# Sheet1.net
KiCad netlist of a schematic drawn in Altium Designer
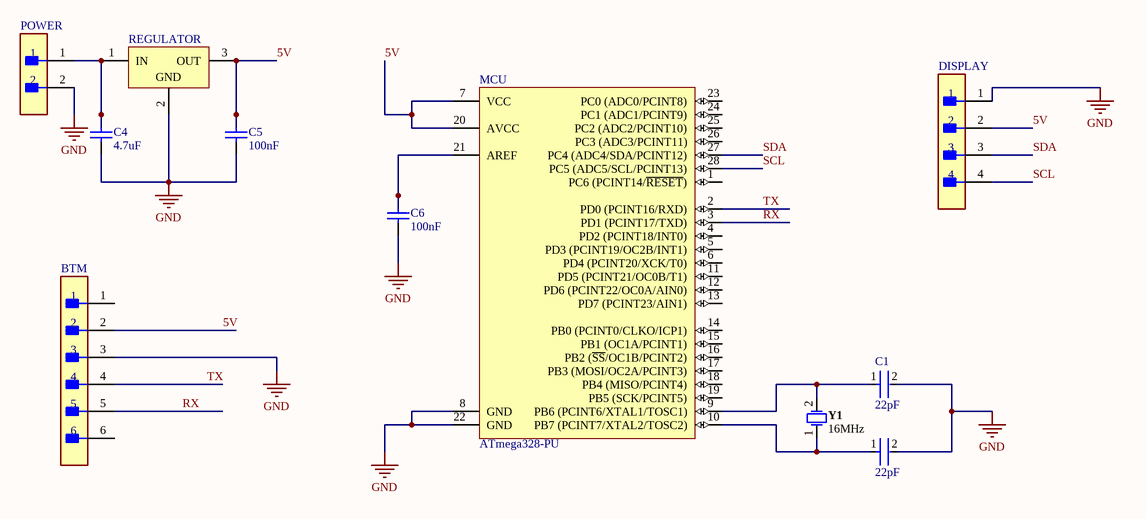
[diagram p0: Sheet1.SchDoc]

(export (version "E")
  (design (tool "Eeschema 10.0.6"))
  (components
    (comp (ref "BTM")
      (value "22-27-2061")
      (footprint "FP-22-27-2061-MFG")
      (description "CONN HEADER VERT 6POS 2.54MM")
      (libsource (lib "Altium Content Vault") (part "f2cb566baf1c37ab5a3b8e90bbeafd6"))
    )
    (comp (ref "C1")
      (value "22pF")
      (footprint "FP-RCE0K1-MFG")
      (description "Cap Ceramic 22pF 50V C0G ±5% Radial 5mm +125°C Automotive Bulk")
      (fields (field (name "TOLERANCE") "5%"))
      (libsource (lib "Altium Content Vault") (part "b4654b650e69147ec39a6b967a45e02"))
    )
    (comp (ref "C2")
      (value "22pF")
      (footprint "FP-RCE0K1-MFG")
      (description "Cap Ceramic 22pF 50V C0G ±5% Radial 5mm +125°C Automotive Bulk")
      (fields (field (name "TOLERANCE") "5%"))
      (libsource (lib "Altium Content Vault") (part "b4654b650e69147ec39a6b967a45e02"))
    )
    (comp (ref "C4")
      (value "4.7uF")
      (footprint "AVX-MD01")
      (description "Ceramic Capacitor, 0.1 uF, +/- 20%, 50 V, -55 to 125 degC, 2-Pin THD (MD01), Bulk")
      (fields (field (name "MANUFACTURER") "AVX"))
      (libsource (lib "Altium Content Vault") (part "CAP-NP-2"))
    )
    (comp (ref "C5")
      (value "100nF")
      (footprint "AVX-MD01")
      (description "Ceramic Capacitor, 0.1 uF, +/- 20%, 50 V, -55 to 125 degC, 2-Pin THD (MD01), Bulk")
      (fields (field (name "MANUFACTURER") "AVX"))
      (libsource (lib "Altium Content Vault") (part "CAP-NP-2"))
    )
    (comp (ref "C6")
      (value "100nF")
      (footprint "AVX-MD01")
      (description "Ceramic Capacitor, 0.1 uF, +/- 20%, 50 V, -55 to 125 degC, 2-Pin THD (MD01), Bulk")
      (fields (field (name "MANUFACTURER") "AVX"))
      (libsource (lib "Altium Content Vault") (part "CAP-NP-2"))
    )
    (comp (ref "DISPLAY")
      (value "LCD DISPLAY")
      (footprint "FP-47053-3000-MFG")
      (description "CONN HEADER VERT 4POS 2.54MM")
      (libsource (lib "Altium Content Vault") (part "299a8cea1bdcbc3624fe62c390fa72c"))
    )
    (comp (ref "MCU")
      (value "ATmega328-PU")
      (footprint "28P3")
      (libsource (lib "Altium Content Vault") (part "MC-8B-ATM48-IL28"))
    )
    (comp (ref "POWER")
      (value "TSW-102-07-L-S")
      (footprint "FP-TSW-102-07-L-S-MFG")
      (description "CONN HEADER VERT 2POS 2.54MM")
      (libsource (lib "Altium Content Vault") (part "3bc925449376181038e59eaffc5286c"))
    )
    (comp (ref "REGULATOR")
      (value "L7805CV")
      (footprint "TO220")
      (description "Positive Voltage Regulator, 5V, 3-Pin TO-220")
      (libsource (lib "Altium Content Vault") (part "PM-REG-L4940-SIL3"))
    )
    (comp (ref "Y1")
      (value "16MHz")
      (footprint "FOX-FOXSLF160-20")
      (description "Resistance Weld Thru-Hole Crystal, 16 MHz, -20 to 70 degC, 2-Pin THD, RoHS, Bulk")
      (fields (field (name "TOLERANCE") "1%"))
      (libsource (lib "Altium Content Vault") (part "XTAL-1-2-2"))
    )
  )
  (nets
    (net (code "1") (name "/5V") (class "Default")
      (node (ref "BTM") (pin "2") (pinfunction "2_2") (pintype "passive"))
      (node (ref "C5") (pin "2") (pinfunction "2_2") (pintype "passive"))
      (node (ref "DISPLAY") (pin "2") (pinfunction "2_2") (pintype "passive"))
      (node (ref "MCU") (pin "20") (pinfunction "AVCC_20") (pintype "power_in"))
      (node (ref "MCU") (pin "7") (pinfunction "VCC_7") (pintype "power_in"))
      (node (ref "REGULATOR") (pin "3") (pinfunction "OUT_3") (pintype "power_in"))
    )
    (net (code "2") (name "/RX") (class "Default")
      (node (ref "BTM") (pin "5") (pinfunction "5_5") (pintype "passive"))
      (node (ref "MCU") (pin "3") (pinfunction "PD1_(PCINT17/TXD)_3") (pintype "bidirectional"))
    )
    (net (code "3") (name "/SCL") (class "Default")
      (node (ref "DISPLAY") (pin "4") (pinfunction "4_4") (pintype "passive"))
      (node (ref "MCU") (pin "28") (pinfunction "PC5_(ADC5/SCL/PCINT13)_28") (pintype "bidirectional"))
    )
    (net (code "4") (name "/SDA") (class "Default")
      (node (ref "DISPLAY") (pin "3") (pinfunction "3_3") (pintype "passive"))
      (node (ref "MCU") (pin "27") (pinfunction "PC4_(ADC4/SDA/PCINT12)_27") (pintype "bidirectional"))
    )
    (net (code "5") (name "/TX") (class "Default")
      (node (ref "BTM") (pin "4") (pinfunction "4_4") (pintype "passive"))
      (node (ref "MCU") (pin "2") (pinfunction "PD0_(PCINT16/RXD)_2") (pintype "bidirectional"))
    )
    (net (code "6") (name "GND") (class "Default")
      (node (ref "BTM") (pin "3") (pinfunction "3_3") (pintype "passive"))
      (node (ref "C1") (pin "2") (pinfunction "2_2") (pintype "passive"))
      (node (ref "C2") (pin "2") (pinfunction "2_2") (pintype "passive"))
      (node (ref "C4") (pin "1") (pinfunction "1_1") (pintype "passive"))
      (node (ref "C5") (pin "1") (pinfunction "1_1") (pintype "passive"))
      (node (ref "C6") (pin "1") (pinfunction "1_1") (pintype "passive"))
      (node (ref "DISPLAY") (pin "1") (pinfunction "1_1") (pintype "passive"))
      (node (ref "MCU") (pin "22") (pinfunction "GND_22") (pintype "power_in"))
      (node (ref "MCU") (pin "8") (pinfunction "GND_8") (pintype "power_in"))
      (node (ref "POWER") (pin "2") (pinfunction "2_2") (pintype "passive"))
      (node (ref "REGULATOR") (pin "2") (pinfunction "GND_2") (pintype "power_in"))
    )
    (net (code "7") (name "Net-(MCU-AREF)") (class "Default")
      (node (ref "C6") (pin "2") (pinfunction "2_2") (pintype "passive"))
      (node (ref "MCU") (pin "21") (pinfunction "AREF_21") (pintype "power_in"))
    )
    (net (code "8") (name "Net-(MCU-PB6_(PCINT6{slash}XTAL1{slash}TOSC1))") (class "Default")
      (node (ref "C1") (pin "1") (pinfunction "1_1") (pintype "passive"))
      (node (ref "MCU") (pin "9") (pinfunction "PB6_(PCINT6/XTAL1/TOSC1)_9") (pintype "bidirectional"))
      (node (ref "Y1") (pin "2") (pinfunction "2_2") (pintype "passive"))
    )
    (net (code "9") (name "Net-(MCU-PB7_(PCINT7{slash}XTAL2{slash}TOSC2))") (class "Default")
      (node (ref "C2") (pin "1") (pinfunction "1_1") (pintype "passive"))
      (node (ref "MCU") (pin "10") (pinfunction "PB7_(PCINT7/XTAL2/TOSC2)_10") (pintype "bidirectional"))
      (node (ref "Y1") (pin "1") (pinfunction "1_1") (pintype "passive"))
    )
    (net (code "10") (name "Net-(REGULATOR-IN)") (class "Default")
      (node (ref "C4") (pin "2") (pinfunction "2_2") (pintype "passive"))
      (node (ref "POWER") (pin "1") (pinfunction "1_1") (pintype "passive"))
      (node (ref "REGULATOR") (pin "1") (pinfunction "IN_1") (pintype "power_in"))
    )
    (net (code "11") (name "unconnected-(BTM-Pad1)") (class "Default")
      (node (ref "BTM") (pin "1") (pinfunction "1_1") (pintype "passive"))
    )
    (net (code "12") (name "unconnected-(BTM-Pad6)") (class "Default")
      (node (ref "BTM") (pin "6") (pinfunction "6_6") (pintype "passive"))
    )
    (net (code "13") (name "unconnected-(MCU-PB0_(PCINT0{slash}CLKO{slash}ICP1)-Pad14)") (class "Default")
      (node (ref "MCU") (pin "14") (pinfunction "PB0_(PCINT0/CLKO/ICP1)_14") (pintype "bidirectional"))
    )
    (net (code "14") (name "unconnected-(MCU-PB1_(OC1A{slash}PCINT1)-Pad15)") (class "Default")
      (node (ref "MCU") (pin "15") (pinfunction "PB1_(OC1A/PCINT1)_15") (pintype "bidirectional"))
    )
    (net (code "15") (name "unconnected-(MCU-PB2_(~{SS}{slash}OC1B{slash}PCINT2)-Pad16)") (class "Default")
      (node (ref "MCU") (pin "16") (pinfunction "PB2_(~{SS}/OC1B/PCINT2)_16") (pintype "bidirectional"))
    )
    (net (code "16") (name "unconnected-(MCU-PB3_(MOSI{slash}OC2A{slash}PCINT3)-Pad17)") (class "Default")
      (node (ref "MCU") (pin "17") (pinfunction "PB3_(MOSI/OC2A/PCINT3)_17") (pintype "bidirectional"))
    )
    (net (code "17") (name "unconnected-(MCU-PB4_(MISO{slash}PCINT4)-Pad18)") (class "Default")
      (node (ref "MCU") (pin "18") (pinfunction "PB4_(MISO/PCINT4)_18") (pintype "bidirectional"))
    )
    (net (code "18") (name "unconnected-(MCU-PB5_(SCK{slash}PCINT5)-Pad19)") (class "Default")
      (node (ref "MCU") (pin "19") (pinfunction "PB5_(SCK/PCINT5)_19") (pintype "bidirectional"))
    )
    (net (code "19") (name "unconnected-(MCU-PC0_(ADC0{slash}PCINT8)-Pad23)") (class "Default")
      (node (ref "MCU") (pin "23") (pinfunction "PC0_(ADC0/PCINT8)_23") (pintype "bidirectional"))
    )
    (net (code "20") (name "unconnected-(MCU-PC1_(ADC1{slash}PCINT9)-Pad24)") (class "Default")
      (node (ref "MCU") (pin "24") (pinfunction "PC1_(ADC1/PCINT9)_24") (pintype "bidirectional"))
    )
    (net (code "21") (name "unconnected-(MCU-PC2_(ADC2{slash}PCINT10)-Pad25)") (class "Default")
      (node (ref "MCU") (pin "25") (pinfunction "PC2_(ADC2/PCINT10)_25") (pintype "bidirectional"))
    )
    (net (code "22") (name "unconnected-(MCU-PC3_(ADC3{slash}PCINT11)-Pad26)") (class "Default")
      (node (ref "MCU") (pin "26") (pinfunction "PC3_(ADC3/PCINT11)_26") (pintype "bidirectional"))
    )
    (net (code "23") (name "unconnected-(MCU-PC6_(PCINT14{slash}~{RESET})-Pad1)") (class "Default")
      (node (ref "MCU") (pin "1") (pinfunction "PC6_(PCINT14/~{RESET})_1") (pintype "bidirectional"))
    )
    (net (code "24") (name "unconnected-(MCU-PD2_(PCINT18{slash}INT0)-Pad4)") (class "Default")
      (node (ref "MCU") (pin "4") (pinfunction "PD2_(PCINT18/INT0)_4") (pintype "bidirectional"))
    )
    (net (code "25") (name "unconnected-(MCU-PD3_(PCINT19{slash}OC2B{slash}INT1)-Pad5)") (class "Default")
      (node (ref "MCU") (pin "5") (pinfunction "PD3_(PCINT19/OC2B/INT1)_5") (pintype "bidirectional"))
    )
    (net (code "26") (name "unconnected-(MCU-PD4_(PCINT20{slash}XCK{slash}T0)-Pad6)") (class "Default")
      (node (ref "MCU") (pin "6") (pinfunction "PD4_(PCINT20/XCK/T0)_6") (pintype "bidirectional"))
    )
    (net (code "27") (name "unconnected-(MCU-PD5_(PCINT21{slash}OC0B{slash}T1)-Pad11)") (class "Default")
      (node (ref "MCU") (pin "11") (pinfunction "PD5_(PCINT21/OC0B/T1)_11") (pintype "bidirectional"))
    )
    (net (code "28") (name "unconnected-(MCU-PD6_(PCINT22{slash}OC0A{slash}AIN0)-Pad12)") (class "Default")
      (node (ref "MCU") (pin "12") (pinfunction "PD6_(PCINT22/OC0A/AIN0)_12") (pintype "bidirectional"))
    )
    (net (code "29") (name "unconnected-(MCU-PD7_(PCINT23{slash}AIN1)-Pad13)") (class "Default")
      (node (ref "MCU") (pin "13") (pinfunction "PD7_(PCINT23/AIN1)_13") (pintype "bidirectional"))
    )
  )
)
